# tc_tp5_ej1.net
KiCad netlist of a schematic drawn in Altium Designer
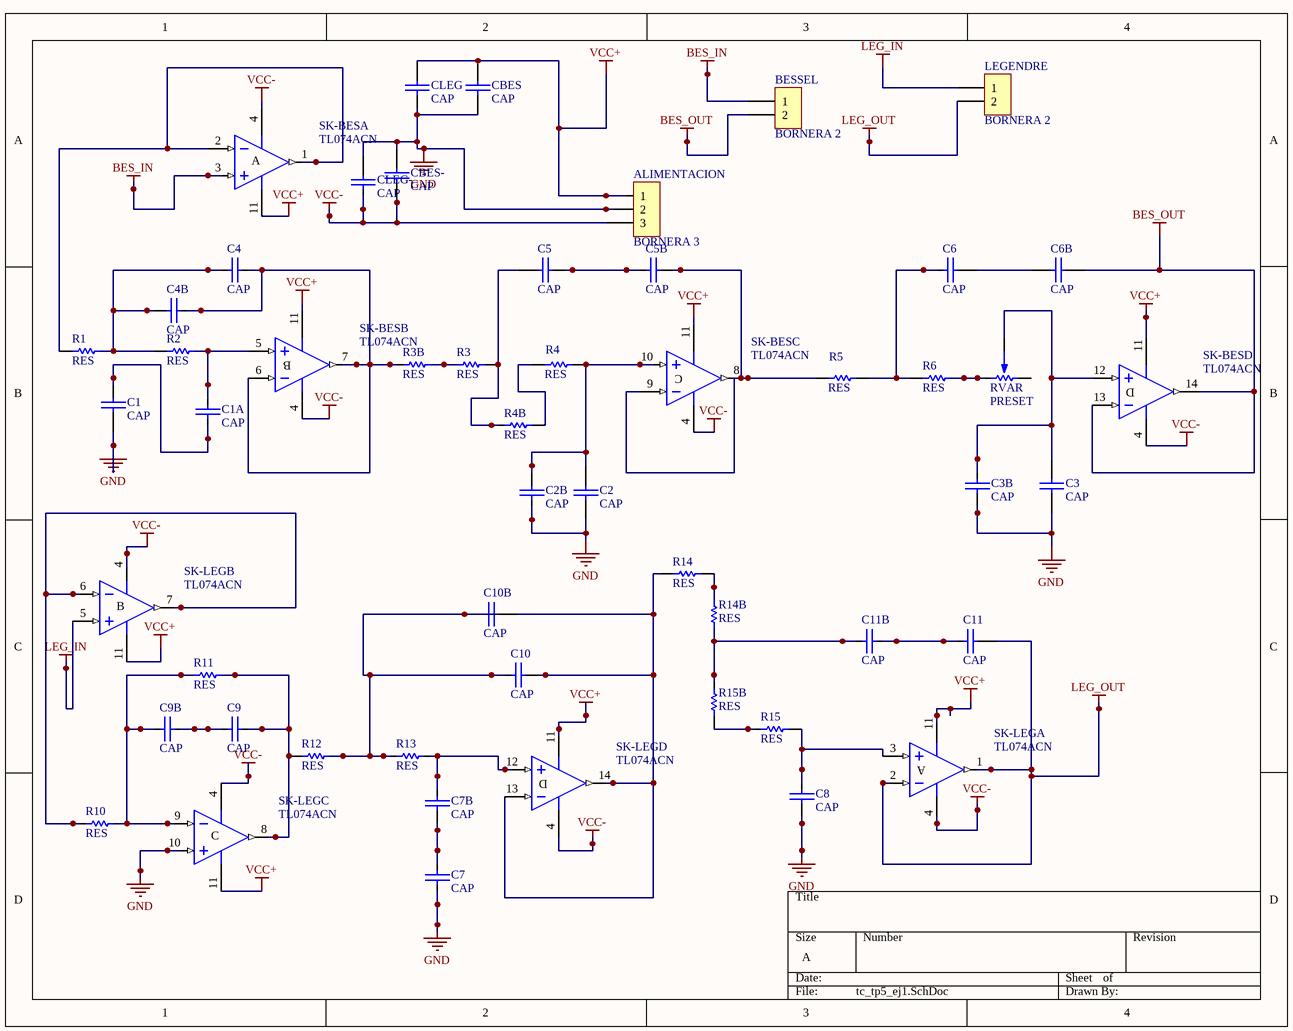
[diagram p0: tc_tp5_ej1.SchDoc]

(export (version "E")
  (design (tool "Eeschema 10.0.6"))
  (components
    (comp (ref "ALIMENTACION")
      (value "BORNERA 3")
      (footprint "BORNERA3")
      (libsource (lib "LIBEBAL") (part "BORNERA 3"))
    )
    (comp (ref "BESSEL")
      (value "BORNERA 2")
      (footprint "BORNERA2")
      (libsource (lib "LIBEBAL") (part "BORNERA 2"))
    )
    (comp (ref "C1") (value "CAP") (footprint "CAP200") (libsource (lib "LIBEBAL") (part "CAP")))
    (comp (ref "C1A") (value "CAP") (footprint "CAP200") (libsource (lib "LIBEBAL") (part "CAP")))
    (comp (ref "C2") (value "CAP") (footprint "CAP200") (libsource (lib "LIBEBAL") (part "CAP")))
    (comp (ref "C2B") (value "CAP") (footprint "CAP200") (libsource (lib "LIBEBAL") (part "CAP")))
    (comp (ref "C3") (value "CAP") (footprint "CAP200") (libsource (lib "LIBEBAL") (part "CAP")))
    (comp (ref "C3B") (value "CAP") (footprint "CAP200") (libsource (lib "LIBEBAL") (part "CAP")))
    (comp (ref "C4") (value "CAP") (footprint "CAP200") (libsource (lib "LIBEBAL") (part "CAP")))
    (comp (ref "C4B") (value "CAP") (footprint "CAP200") (libsource (lib "LIBEBAL") (part "CAP")))
    (comp (ref "C5") (value "CAP") (footprint "CAP200") (libsource (lib "LIBEBAL") (part "CAP")))
    (comp (ref "C5B") (value "CAP") (footprint "CAP200") (libsource (lib "LIBEBAL") (part "CAP")))
    (comp (ref "C6") (value "CAP") (footprint "CAP200") (libsource (lib "LIBEBAL") (part "CAP")))
    (comp (ref "C6B") (value "CAP") (footprint "CAP200") (libsource (lib "LIBEBAL") (part "CAP")))
    (comp (ref "C7") (value "CAP") (footprint "CAP200") (libsource (lib "LIBEBAL") (part "CAP")))
    (comp (ref "C7B") (value "CAP") (footprint "CAP200") (libsource (lib "LIBEBAL") (part "CAP")))
    (comp (ref "C8") (value "CAP") (footprint "CAP200") (libsource (lib "LIBEBAL") (part "CAP")))
    (comp (ref "C9") (value "CAP") (footprint "CAP200") (libsource (lib "LIBEBAL") (part "CAP")))
    (comp (ref "C9B") (value "CAP") (footprint "CAP200") (libsource (lib "LIBEBAL") (part "CAP")))
    (comp (ref "C10") (value "CAP") (footprint "CAP200") (libsource (lib "LIBEBAL") (part "CAP")))
    (comp (ref "C10B") (value "CAP") (footprint "CAP200") (libsource (lib "LIBEBAL") (part "CAP")))
    (comp (ref "C11") (value "CAP") (footprint "CAP200") (libsource (lib "LIBEBAL") (part "CAP")))
    (comp (ref "C11B") (value "CAP") (footprint "CAP200") (libsource (lib "LIBEBAL") (part "CAP")))
    (comp (ref "CBES") (value "CAP") (footprint "CAP200") (libsource (lib "LIBEBAL") (part "CAP")))
    (comp (ref "CBES-") (value "CAP") (footprint "CAP200") (libsource (lib "LIBEBAL") (part "CAP")))
    (comp (ref "CLEG") (value "CAP") (footprint "CAP200") (libsource (lib "LIBEBAL") (part "CAP")))
    (comp (ref "CLEG-") (value "CAP") (footprint "CAP200") (libsource (lib "LIBEBAL") (part "CAP")))
    (comp (ref "LEGENDRE")
      (value "BORNERA 2")
      (footprint "BORNERA2")
      (libsource (lib "LIBEBAL") (part "BORNERA 2"))
    )
    (comp (ref "R1") (value "RES") (footprint "0805") (libsource (lib "LIBEBAL") (part "RES")))
    (comp (ref "R2") (value "RES") (footprint "0805") (libsource (lib "LIBEBAL") (part "RES")))
    (comp (ref "R3") (value "RES") (footprint "0805") (libsource (lib "LIBEBAL") (part "RES")))
    (comp (ref "R3B") (value "RES") (footprint "0805") (libsource (lib "LIBEBAL") (part "RES")))
    (comp (ref "R4") (value "RES") (footprint "0805") (libsource (lib "LIBEBAL") (part "RES")))
    (comp (ref "R4B") (value "RES") (footprint "0805") (libsource (lib "LIBEBAL") (part "RES")))
    (comp (ref "R5") (value "RES") (footprint "0805") (libsource (lib "LIBEBAL") (part "RES")))
    (comp (ref "R6") (value "RES") (footprint "0805") (libsource (lib "LIBEBAL") (part "RES")))
    (comp (ref "R10") (value "RES") (footprint "0805") (libsource (lib "LIBEBAL") (part "RES")))
    (comp (ref "R11") (value "RES") (footprint "0805") (libsource (lib "LIBEBAL") (part "RES")))
    (comp (ref "R12") (value "RES") (footprint "0805") (libsource (lib "LIBEBAL") (part "RES")))
    (comp (ref "R13") (value "RES") (footprint "0805") (libsource (lib "LIBEBAL") (part "RES")))
    (comp (ref "R14") (value "RES") (footprint "0805") (libsource (lib "LIBEBAL") (part "RES")))
    (comp (ref "R14B") (value "RES") (footprint "0805") (libsource (lib "LIBEBAL") (part "RES")))
    (comp (ref "R15") (value "RES") (footprint "0805") (libsource (lib "LIBEBAL") (part "RES")))
    (comp (ref "R15B") (value "RES") (footprint "0805") (libsource (lib "LIBEBAL") (part "RES")))
    (comp (ref "RVAR") (value "PRESET") (footprint "PRESET H") (libsource (lib "LIBEBAL") (part "PRESET")))
    (comp (ref "SK-BES")
      (value "TL074ACN")
      (footprint "DIP14")
      (description "Low-Noise J-FET Quad Operational Amplifier")
      (fields (field (name "PUBLISHER") "Altium Limited"))
      (libsource (lib "ST Operational Amplifier") (part "TL074ACN"))
    )
    (comp (ref "SK-LEG")
      (value "TL074ACN")
      (footprint "DIP14")
      (description "Low-Noise J-FET Quad Operational Amplifier")
      (fields (field (name "PUBLISHER") "Altium Limited"))
      (libsource (lib "ST Operational Amplifier") (part "TL074ACN"))
    )
  )
  (nets
    (net (code "1") (name "BES_IN") (class "Default")
      (node (ref "BESSEL") (pin "1") (pinfunction "1_1") (pintype "passive"))
      (node (ref "SK-BES") (pin "3") (pinfunction "IN+_3") (pintype "input"))
    )
    (net (code "2") (name "BES_OUT") (class "Default")
      (node (ref "BESSEL") (pin "2") (pinfunction "2_2") (pintype "passive"))
      (node (ref "C6B") (pin "1") (pinfunction "1_1") (pintype "passive"))
      (node (ref "SK-BES") (pin "13") (pinfunction "IN-_13") (pintype "input"))
      (node (ref "SK-BES") (pin "14") (pinfunction "OUT_14") (pintype "output"))
    )
    (net (code "3") (name "GND") (class "Default")
      (node (ref "ALIMENTACION") (pin "2") (pinfunction "2_2") (pintype "passive"))
      (node (ref "C1") (pin "2") (pinfunction "2_2") (pintype "passive"))
      (node (ref "C2") (pin "2") (pinfunction "2_2") (pintype "passive"))
      (node (ref "C2B") (pin "2") (pinfunction "2_2") (pintype "passive"))
      (node (ref "C3") (pin "2") (pinfunction "2_2") (pintype "passive"))
      (node (ref "C3B") (pin "1") (pinfunction "1_1") (pintype "passive"))
      (node (ref "C7") (pin "1") (pinfunction "1_1") (pintype "passive"))
      (node (ref "C8") (pin "1") (pinfunction "1_1") (pintype "passive"))
      (node (ref "CBES") (pin "2") (pinfunction "2_2") (pintype "passive"))
      (node (ref "CBES-") (pin "1") (pinfunction "1_1") (pintype "passive"))
      (node (ref "CLEG") (pin "2") (pinfunction "2_2") (pintype "passive"))
      (node (ref "CLEG-") (pin "1") (pinfunction "1_1") (pintype "passive"))
      (node (ref "SK-LEG") (pin "10") (pinfunction "IN+_10") (pintype "input"))
    )
    (net (code "4") (name "LEG_IN") (class "Default")
      (node (ref "LEGENDRE") (pin "1") (pinfunction "1_1") (pintype "passive"))
      (node (ref "SK-LEG") (pin "5") (pinfunction "IN+_5") (pintype "input"))
    )
    (net (code "5") (name "LEG_OUT") (class "Default")
      (node (ref "C11") (pin "2") (pinfunction "2_2") (pintype "passive"))
      (node (ref "LEGENDRE") (pin "2") (pinfunction "2_2") (pintype "passive"))
      (node (ref "SK-LEG") (pin "1") (pinfunction "OUT_1") (pintype "output"))
      (node (ref "SK-LEG") (pin "2") (pinfunction "IN-_2") (pintype "input"))
    )
    (net (code "6") (name "Net-(C1-Pad1)") (class "Default")
      (node (ref "C1") (pin "1") (pinfunction "1_1") (pintype "passive"))
      (node (ref "C1A") (pin "1") (pinfunction "1_1") (pintype "passive"))
    )
    (net (code "7") (name "Net-(C4-Pad1)") (class "Default")
      (node (ref "C4") (pin "1") (pinfunction "1_1") (pintype "passive"))
      (node (ref "C4B") (pin "2") (pinfunction "2_2") (pintype "passive"))
      (node (ref "R1") (pin "2") (pinfunction "2_2") (pintype "passive"))
      (node (ref "R2") (pin "1") (pinfunction "1_1") (pintype "passive"))
    )
    (net (code "8") (name "Net-(C5-Pad1)") (class "Default")
      (node (ref "C5") (pin "1") (pinfunction "1_1") (pintype "passive"))
      (node (ref "R3") (pin "2") (pinfunction "2_2") (pintype "passive"))
      (node (ref "R4B") (pin "1") (pinfunction "1_1") (pintype "passive"))
    )
    (net (code "9") (name "Net-(C5-Pad2)") (class "Default")
      (node (ref "C5") (pin "2") (pinfunction "2_2") (pintype "passive"))
      (node (ref "C5B") (pin "1") (pinfunction "1_1") (pintype "passive"))
    )
    (net (code "10") (name "Net-(C6-Pad1)") (class "Default")
      (node (ref "C6") (pin "1") (pinfunction "1_1") (pintype "passive"))
      (node (ref "R5") (pin "2") (pinfunction "2_2") (pintype "passive"))
      (node (ref "R6") (pin "1") (pinfunction "1_1") (pintype "passive"))
    )
    (net (code "11") (name "Net-(C6-Pad2)") (class "Default")
      (node (ref "C6") (pin "2") (pinfunction "2_2") (pintype "passive"))
      (node (ref "C6B") (pin "2") (pinfunction "2_2") (pintype "passive"))
    )
    (net (code "12") (name "Net-(C7-Pad2)") (class "Default")
      (node (ref "C7") (pin "2") (pinfunction "2_2") (pintype "passive"))
      (node (ref "C7B") (pin "1") (pinfunction "1_1") (pintype "passive"))
    )
    (net (code "13") (name "Net-(C9-Pad1)") (class "Default")
      (node (ref "C9") (pin "1") (pinfunction "1_1") (pintype "passive"))
      (node (ref "C9B") (pin "2") (pinfunction "2_2") (pintype "passive"))
    )
    (net (code "14") (name "Net-(C10-Pad1)") (class "Default")
      (node (ref "C10") (pin "1") (pinfunction "1_1") (pintype "passive"))
      (node (ref "C10B") (pin "1") (pinfunction "1_1") (pintype "passive"))
      (node (ref "R12") (pin "2") (pinfunction "2_2") (pintype "passive"))
      (node (ref "R13") (pin "1") (pinfunction "1_1") (pintype "passive"))
    )
    (net (code "15") (name "Net-(C11-Pad1)") (class "Default")
      (node (ref "C11") (pin "1") (pinfunction "1_1") (pintype "passive"))
      (node (ref "C11B") (pin "1") (pinfunction "1_1") (pintype "passive"))
    )
    (net (code "16") (name "Net-(C11B-Pad2)") (class "Default")
      (node (ref "C11B") (pin "2") (pinfunction "2_2") (pintype "passive"))
      (node (ref "R14B") (pin "1") (pinfunction "1_1") (pintype "passive"))
      (node (ref "R15B") (pin "1") (pinfunction "1_1") (pintype "passive"))
    )
    (net (code "17") (name "Net-(R3-Pad1)") (class "Default")
      (node (ref "R3") (pin "1") (pinfunction "1_1") (pintype "passive"))
      (node (ref "R3B") (pin "2") (pinfunction "2_2") (pintype "passive"))
    )
    (net (code "18") (name "Net-(R4-Pad1)") (class "Default")
      (node (ref "R4") (pin "1") (pinfunction "1_1") (pintype "passive"))
      (node (ref "R4B") (pin "2") (pinfunction "2_2") (pintype "passive"))
    )
    (net (code "19") (name "Net-(R6-Pad2)") (class "Default")
      (node (ref "R6") (pin "2") (pinfunction "2_2") (pintype "passive"))
      (node (ref "RVAR") (pin "1") (pinfunction "1_1") (pintype "passive"))
    )
    (net (code "20") (name "Net-(R14-Pad1)") (class "Default")
      (node (ref "R14") (pin "1") (pinfunction "1_1") (pintype "passive"))
      (node (ref "R14B") (pin "2") (pinfunction "2_2") (pintype "passive"))
    )
    (net (code "21") (name "Net-(R15-Pad1)") (class "Default")
      (node (ref "R15") (pin "1") (pinfunction "1_1") (pintype "passive"))
      (node (ref "R15B") (pin "2") (pinfunction "2_2") (pintype "passive"))
    )
    (net (code "22") (name "Net-(SK-BESA-IN-)") (class "Default")
      (node (ref "R1") (pin "1") (pinfunction "1_1") (pintype "passive"))
      (node (ref "SK-BES") (pin "1") (pinfunction "OUT_1") (pintype "output"))
      (node (ref "SK-BES") (pin "2") (pinfunction "IN-_2") (pintype "input"))
    )
    (net (code "23") (name "Net-(SK-BESB-IN+)") (class "Default")
      (node (ref "C1A") (pin "2") (pinfunction "2_2") (pintype "passive"))
      (node (ref "R2") (pin "2") (pinfunction "2_2") (pintype "passive"))
      (node (ref "SK-BES") (pin "5") (pinfunction "IN+_5") (pintype "input"))
    )
    (net (code "24") (name "Net-(SK-BESB-IN-)") (class "Default")
      (node (ref "C4") (pin "2") (pinfunction "2_2") (pintype "passive"))
      (node (ref "C4B") (pin "1") (pinfunction "1_1") (pintype "passive"))
      (node (ref "R3B") (pin "1") (pinfunction "1_1") (pintype "passive"))
      (node (ref "SK-BES") (pin "6") (pinfunction "IN-_6") (pintype "input"))
      (node (ref "SK-BES") (pin "7") (pinfunction "OUT_7") (pintype "output"))
    )
    (net (code "25") (name "Net-(SK-BESC-IN+)") (class "Default")
      (node (ref "C2") (pin "1") (pinfunction "1_1") (pintype "passive"))
      (node (ref "C2B") (pin "1") (pinfunction "1_1") (pintype "passive"))
      (node (ref "R4") (pin "2") (pinfunction "2_2") (pintype "passive"))
      (node (ref "SK-BES") (pin "10") (pinfunction "IN+_10") (pintype "input"))
    )
    (net (code "26") (name "Net-(SK-BESC-IN-)") (class "Default")
      (node (ref "C5B") (pin "2") (pinfunction "2_2") (pintype "passive"))
      (node (ref "R5") (pin "1") (pinfunction "1_1") (pintype "passive"))
      (node (ref "SK-BES") (pin "8") (pinfunction "OUT_8") (pintype "output"))
      (node (ref "SK-BES") (pin "9") (pinfunction "IN-_9") (pintype "input"))
    )
    (net (code "27") (name "Net-(SK-BESD-IN+)") (class "Default")
      (node (ref "C3") (pin "1") (pinfunction "1_1") (pintype "passive"))
      (node (ref "C3B") (pin "2") (pinfunction "2_2") (pintype "passive"))
      (node (ref "RVAR") (pin "2") (pinfunction "2_2") (pintype "passive"))
      (node (ref "SK-BES") (pin "12") (pinfunction "IN+_12") (pintype "input"))
    )
    (net (code "28") (name "Net-(SK-LEGA-IN+)") (class "Default")
      (node (ref "C8") (pin "2") (pinfunction "2_2") (pintype "passive"))
      (node (ref "R15") (pin "2") (pinfunction "2_2") (pintype "passive"))
      (node (ref "SK-LEG") (pin "3") (pinfunction "IN+_3") (pintype "input"))
    )
    (net (code "29") (name "Net-(SK-LEGB-IN-)") (class "Default")
      (node (ref "R10") (pin "1") (pinfunction "1_1") (pintype "passive"))
      (node (ref "SK-LEG") (pin "6") (pinfunction "IN-_6") (pintype "input"))
      (node (ref "SK-LEG") (pin "7") (pinfunction "OUT_7") (pintype "output"))
    )
    (net (code "30") (name "Net-(SK-LEGC-IN-)") (class "Default")
      (node (ref "C9B") (pin "1") (pinfunction "1_1") (pintype "passive"))
      (node (ref "R10") (pin "2") (pinfunction "2_2") (pintype "passive"))
      (node (ref "R11") (pin "1") (pinfunction "1_1") (pintype "passive"))
      (node (ref "SK-LEG") (pin "9") (pinfunction "IN-_9") (pintype "input"))
    )
    (net (code "31") (name "Net-(SK-LEGC-OUT)") (class "Default")
      (node (ref "C9") (pin "2") (pinfunction "2_2") (pintype "passive"))
      (node (ref "R11") (pin "2") (pinfunction "2_2") (pintype "passive"))
      (node (ref "R12") (pin "1") (pinfunction "1_1") (pintype "passive"))
      (node (ref "SK-LEG") (pin "8") (pinfunction "OUT_8") (pintype "output"))
    )
    (net (code "32") (name "Net-(SK-LEGD-IN+)") (class "Default")
      (node (ref "C7B") (pin "2") (pinfunction "2_2") (pintype "passive"))
      (node (ref "R13") (pin "2") (pinfunction "2_2") (pintype "passive"))
      (node (ref "SK-LEG") (pin "12") (pinfunction "IN+_12") (pintype "input"))
    )
    (net (code "33") (name "Net-(SK-LEGD-IN-)") (class "Default")
      (node (ref "C10") (pin "2") (pinfunction "2_2") (pintype "passive"))
      (node (ref "C10B") (pin "2") (pinfunction "2_2") (pintype "passive"))
      (node (ref "R14") (pin "2") (pinfunction "2_2") (pintype "passive"))
      (node (ref "SK-LEG") (pin "13") (pinfunction "IN-_13") (pintype "input"))
      (node (ref "SK-LEG") (pin "14") (pinfunction "OUT_14") (pintype "output"))
    )
    (net (code "34") (name "VCC+") (class "Default")
      (node (ref "ALIMENTACION") (pin "1") (pinfunction "1_1") (pintype "passive"))
      (node (ref "CBES") (pin "1") (pinfunction "1_1") (pintype "passive"))
      (node (ref "CLEG") (pin "1") (pinfunction "1_1") (pintype "passive"))
      (node (ref "SK-BES") (pin "11") (pinfunction "V-_11") (pintype "power_in"))
      (node (ref "SK-LEG") (pin "11") (pinfunction "V-_11") (pintype "power_in"))
    )
    (net (code "35") (name "VCC-") (class "Default")
      (node (ref "ALIMENTACION") (pin "3") (pinfunction "3_3") (pintype "passive"))
      (node (ref "CBES-") (pin "2") (pinfunction "2_2") (pintype "passive"))
      (node (ref "CLEG-") (pin "2") (pinfunction "2_2") (pintype "passive"))
      (node (ref "SK-BES") (pin "4") (pinfunction "V+_4") (pintype "power_in"))
      (node (ref "SK-LEG") (pin "4") (pinfunction "V+_4") (pintype "power_in"))
    )
    (net (code "36") (name "unconnected-(RVAR-Pad3)") (class "Default")
      (node (ref "RVAR") (pin "3") (pinfunction "3_3") (pintype "passive"))
    )
  )
)
